# middle.net
KiCad netlist of a schematic drawn in Altium Designer
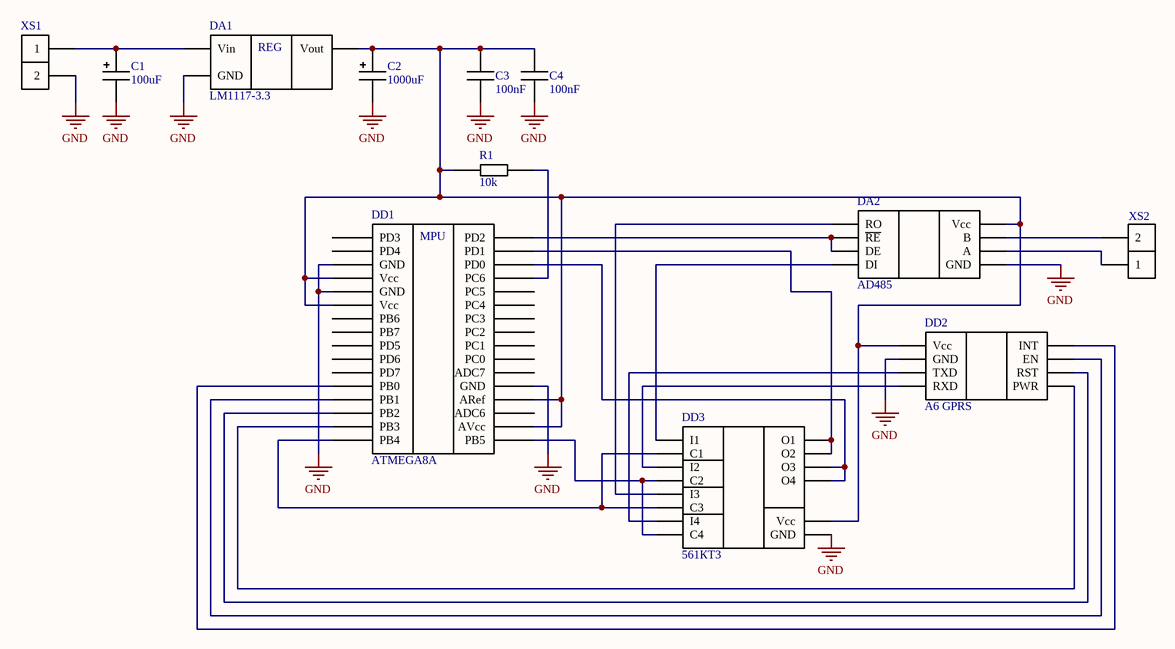
[diagram p0: middle.SchDoc]

(export (version "E")
  (design (tool "Eeschema 10.0.6"))
  (components
    (comp (ref "C1") (value "100uF") (libsource (lib "EDDLib") (part "CAP_POLAR")))
    (comp (ref "C2") (value "1000uF") (libsource (lib "EDDLib") (part "CAP_POLAR")))
    (comp (ref "C3") (value "100nF") (libsource (lib "EDDLib") (part "CAP_NONPOLAR")))
    (comp (ref "C4") (value "100nF") (libsource (lib "EDDLib") (part "CAP_NONPOLAR")))
    (comp (ref "DA1") (value "LM1117-3.3") (libsource (lib "EDDLib") (part "LM1117-3.3")))
    (comp (ref "DA2") (value "AD485") (libsource (lib "EDDLib") (part "AD485")))
    (comp (ref "DD1") (value "ATMEGA8A") (libsource (lib "EDDLib") (part "ATMEGA8A")))
    (comp (ref "DD2") (value "A6 GPRS") (libsource (lib "EDDLib") (part "A6 GPRS")))
    (comp (ref "DD3") (value "561КТ3") (libsource (lib "EDDLib") (part "561КТ3")))
    (comp (ref "R1") (value "10k") (libsource (lib "EDDLib") (part "RES")))
    (comp (ref "XS1") (value "CONN-2") (libsource (lib "EDDLib") (part "CONN-2")))
    (comp (ref "XS2") (value "CONN-2") (libsource (lib "EDDLib") (part "CONN-2")))
  )
  (nets
    (net (code "1") (name "GND") (class "Default")
      (node (ref "C1") (pin "2") (pinfunction "2_2") (pintype "passive"))
      (node (ref "C2") (pin "2") (pinfunction "2_2") (pintype "passive"))
      (node (ref "C3") (pin "2") (pinfunction "2_2") (pintype "passive"))
      (node (ref "C4") (pin "2") (pinfunction "2_2") (pintype "passive"))
      (node (ref "DA1") (pin "3") (pinfunction "GND_3") (pintype "passive"))
      (node (ref "DA2") (pin "5") (pinfunction "GND_5") (pintype "passive"))
      (node (ref "DD1") (pin "21") (pinfunction "GND_21") (pintype "passive"))
      (node (ref "DD1") (pin "3") (pinfunction "GND_3") (pintype "passive"))
      (node (ref "DD1") (pin "5") (pinfunction "GND_5") (pintype "passive"))
      (node (ref "DD2") (pin "2") (pinfunction "GND_2") (pintype "passive"))
      (node (ref "DD3") (pin "7") (pinfunction "GND_7") (pintype "passive"))
      (node (ref "XS1") (pin "2") (pinfunction "2_2") (pintype "passive"))
    )
    (net (code "2") (name "Net-(DA1-Vin)") (class "Default")
      (node (ref "C1") (pin "1") (pinfunction "1_1") (pintype "passive"))
      (node (ref "DA1") (pin "1") (pinfunction "Vin_1") (pintype "passive"))
      (node (ref "XS1") (pin "1") (pinfunction "1_1") (pintype "passive"))
    )
    (net (code "3") (name "Net-(DA1-Vout)") (class "Default")
      (node (ref "C2") (pin "1") (pinfunction "1_1") (pintype "passive"))
      (node (ref "C3") (pin "1") (pinfunction "1_1") (pintype "passive"))
      (node (ref "C4") (pin "1") (pinfunction "1_1") (pintype "passive"))
      (node (ref "DA1") (pin "2") (pinfunction "Vout_2") (pintype "passive"))
      (node (ref "DA2") (pin "8") (pinfunction "Vcc_8") (pintype "passive"))
      (node (ref "DD1") (pin "18") (pinfunction "AVcc_18") (pintype "passive"))
      (node (ref "DD1") (pin "20") (pinfunction "ARef_20") (pintype "passive"))
      (node (ref "DD1") (pin "4") (pinfunction "Vcc_4") (pintype "passive"))
      (node (ref "DD1") (pin "6") (pinfunction "Vcc_6") (pintype "passive"))
      (node (ref "DD2") (pin "1") (pinfunction "Vcc_1") (pintype "passive"))
      (node (ref "DD3") (pin "14") (pinfunction "Vcc_14") (pintype "passive"))
      (node (ref "R1") (pin "2") (pinfunction "2_2") (pintype "passive"))
    )
    (net (code "4") (name "Net-(DA2-A)") (class "Default")
      (node (ref "DA2") (pin "6") (pinfunction "A_6") (pintype "passive"))
      (node (ref "XS2") (pin "1") (pinfunction "1_1") (pintype "passive"))
    )
    (net (code "5") (name "Net-(DA2-B)") (class "Default")
      (node (ref "DA2") (pin "7") (pinfunction "B_7") (pintype "passive"))
      (node (ref "XS2") (pin "2") (pinfunction "2_2") (pintype "passive"))
    )
    (net (code "6") (name "Net-(DA2-DE)") (class "Default")
      (node (ref "DA2") (pin "2") (pinfunction "~{RE}_2") (pintype "passive"))
      (node (ref "DA2") (pin "3") (pinfunction "DE_3") (pintype "passive"))
      (node (ref "DD1") (pin "32") (pinfunction "PD2_32") (pintype "passive"))
    )
    (net (code "7") (name "Net-(DA2-DI)") (class "Default")
      (node (ref "DA2") (pin "4") (pinfunction "DI_4") (pintype "passive"))
      (node (ref "DD3") (pin "1") (pinfunction "I1_1") (pintype "passive"))
    )
    (net (code "8") (name "Net-(DA2-RO)") (class "Default")
      (node (ref "DA2") (pin "1") (pinfunction "RO_1") (pintype "passive"))
      (node (ref "DD3") (pin "4") (pinfunction "I3_4") (pintype "passive"))
    )
    (net (code "9") (name "Net-(DD1-PB0)") (class "Default")
      (node (ref "DD1") (pin "12") (pinfunction "PB0_12") (pintype "passive"))
      (node (ref "DD2") (pin "8") (pinfunction "INT_8") (pintype "passive"))
    )
    (net (code "10") (name "Net-(DD1-PB1)") (class "Default")
      (node (ref "DD1") (pin "13") (pinfunction "PB1_13") (pintype "passive"))
      (node (ref "DD2") (pin "7") (pinfunction "EN_7") (pintype "passive"))
    )
    (net (code "11") (name "Net-(DD1-PB2)") (class "Default")
      (node (ref "DD1") (pin "14") (pinfunction "PB2_14") (pintype "passive"))
      (node (ref "DD2") (pin "6") (pinfunction "RST_6") (pintype "passive"))
    )
    (net (code "12") (name "Net-(DD1-PB3)") (class "Default")
      (node (ref "DD1") (pin "15") (pinfunction "PB3_15") (pintype "passive"))
      (node (ref "DD2") (pin "5") (pinfunction "PWR_5") (pintype "passive"))
    )
    (net (code "13") (name "Net-(DD1-PB4)") (class "Default")
      (node (ref "DD1") (pin "16") (pinfunction "PB4_16") (pintype "passive"))
      (node (ref "DD3") (pin "2") (pinfunction "C1_2") (pintype "passive"))
      (node (ref "DD3") (pin "5") (pinfunction "C3_5") (pintype "passive"))
    )
    (net (code "14") (name "Net-(DD1-PB5)") (class "Default")
      (node (ref "DD1") (pin "17") (pinfunction "PB5_17") (pintype "passive"))
      (node (ref "DD3") (pin "12") (pinfunction "C2_12") (pintype "passive"))
      (node (ref "DD3") (pin "6") (pinfunction "C4_6") (pintype "passive"))
    )
    (net (code "15") (name "Net-(DD1-PC6)") (class "Default")
      (node (ref "DD1") (pin "29") (pinfunction "PC6_29") (pintype "passive"))
      (node (ref "R1") (pin "1") (pinfunction "1_1") (pintype "passive"))
    )
    (net (code "16") (name "Net-(DD1-PD0)") (class "Default")
      (node (ref "DD1") (pin "30") (pinfunction "PD0_30") (pintype "passive"))
      (node (ref "DD3") (pin "3") (pinfunction "O3_3") (pintype "passive"))
      (node (ref "DD3") (pin "9") (pinfunction "O4_9") (pintype "passive"))
    )
    (net (code "17") (name "Net-(DD1-PD1)") (class "Default")
      (node (ref "DD1") (pin "31") (pinfunction "PD1_31") (pintype "passive"))
      (node (ref "DD3") (pin "10") (pinfunction "O2_10") (pintype "passive"))
      (node (ref "DD3") (pin "2") (pinfunction "O1_2") (pintype "passive"))
    )
    (net (code "18") (name "Net-(DD2-RXD)") (class "Default")
      (node (ref "DD2") (pin "4") (pinfunction "RXD_4") (pintype "passive"))
      (node (ref "DD3") (pin "11") (pinfunction "I2_11") (pintype "passive"))
    )
    (net (code "19") (name "Net-(DD2-TXD)") (class "Default")
      (node (ref "DD2") (pin "3") (pinfunction "TXD_3") (pintype "passive"))
      (node (ref "DD3") (pin "8") (pinfunction "I4_8") (pintype "passive"))
    )
    (net (code "20") (name "unconnected-(DD1-ADC6-Pad19)") (class "Default")
      (node (ref "DD1") (pin "19") (pinfunction "ADC6_19") (pintype "passive"))
    )
    (net (code "21") (name "unconnected-(DD1-ADC7-Pad22)") (class "Default")
      (node (ref "DD1") (pin "22") (pinfunction "ADC7_22") (pintype "passive"))
    )
    (net (code "22") (name "unconnected-(DD1-PB6-Pad7)") (class "Default")
      (node (ref "DD1") (pin "7") (pinfunction "PB6_7") (pintype "passive"))
    )
    (net (code "23") (name "unconnected-(DD1-PB7-Pad8)") (class "Default")
      (node (ref "DD1") (pin "8") (pinfunction "PB7_8") (pintype "passive"))
    )
    (net (code "24") (name "unconnected-(DD1-PC0-Pad23)") (class "Default")
      (node (ref "DD1") (pin "23") (pinfunction "PC0_23") (pintype "passive"))
    )
    (net (code "25") (name "unconnected-(DD1-PC1-Pad24)") (class "Default")
      (node (ref "DD1") (pin "24") (pinfunction "PC1_24") (pintype "passive"))
    )
    (net (code "26") (name "unconnected-(DD1-PC2-Pad25)") (class "Default")
      (node (ref "DD1") (pin "25") (pinfunction "PC2_25") (pintype "passive"))
    )
    (net (code "27") (name "unconnected-(DD1-PC3-Pad26)") (class "Default")
      (node (ref "DD1") (pin "26") (pinfunction "PC3_26") (pintype "passive"))
    )
    (net (code "28") (name "unconnected-(DD1-PC4-Pad27)") (class "Default")
      (node (ref "DD1") (pin "27") (pinfunction "PC4_27") (pintype "passive"))
    )
    (net (code "29") (name "unconnected-(DD1-PC5-Pad28)") (class "Default")
      (node (ref "DD1") (pin "28") (pinfunction "PC5_28") (pintype "passive"))
    )
    (net (code "30") (name "unconnected-(DD1-PD3-Pad1)") (class "Default")
      (node (ref "DD1") (pin "1") (pinfunction "PD3_1") (pintype "passive"))
    )
    (net (code "31") (name "unconnected-(DD1-PD4-Pad2)") (class "Default")
      (node (ref "DD1") (pin "2") (pinfunction "PD4_2") (pintype "passive"))
    )
    (net (code "32") (name "unconnected-(DD1-PD5-Pad9)") (class "Default")
      (node (ref "DD1") (pin "9") (pinfunction "PD5_9") (pintype "passive"))
    )
    (net (code "33") (name "unconnected-(DD1-PD6-Pad10)") (class "Default")
      (node (ref "DD1") (pin "10") (pinfunction "PD6_10") (pintype "passive"))
    )
    (net (code "34") (name "unconnected-(DD1-PD7-Pad11)") (class "Default")
      (node (ref "DD1") (pin "11") (pinfunction "PD7_11") (pintype "passive"))
    )
  )
)
